# FAIO-Switch.net
KiCad netlist of a schematic drawn in EAGLE
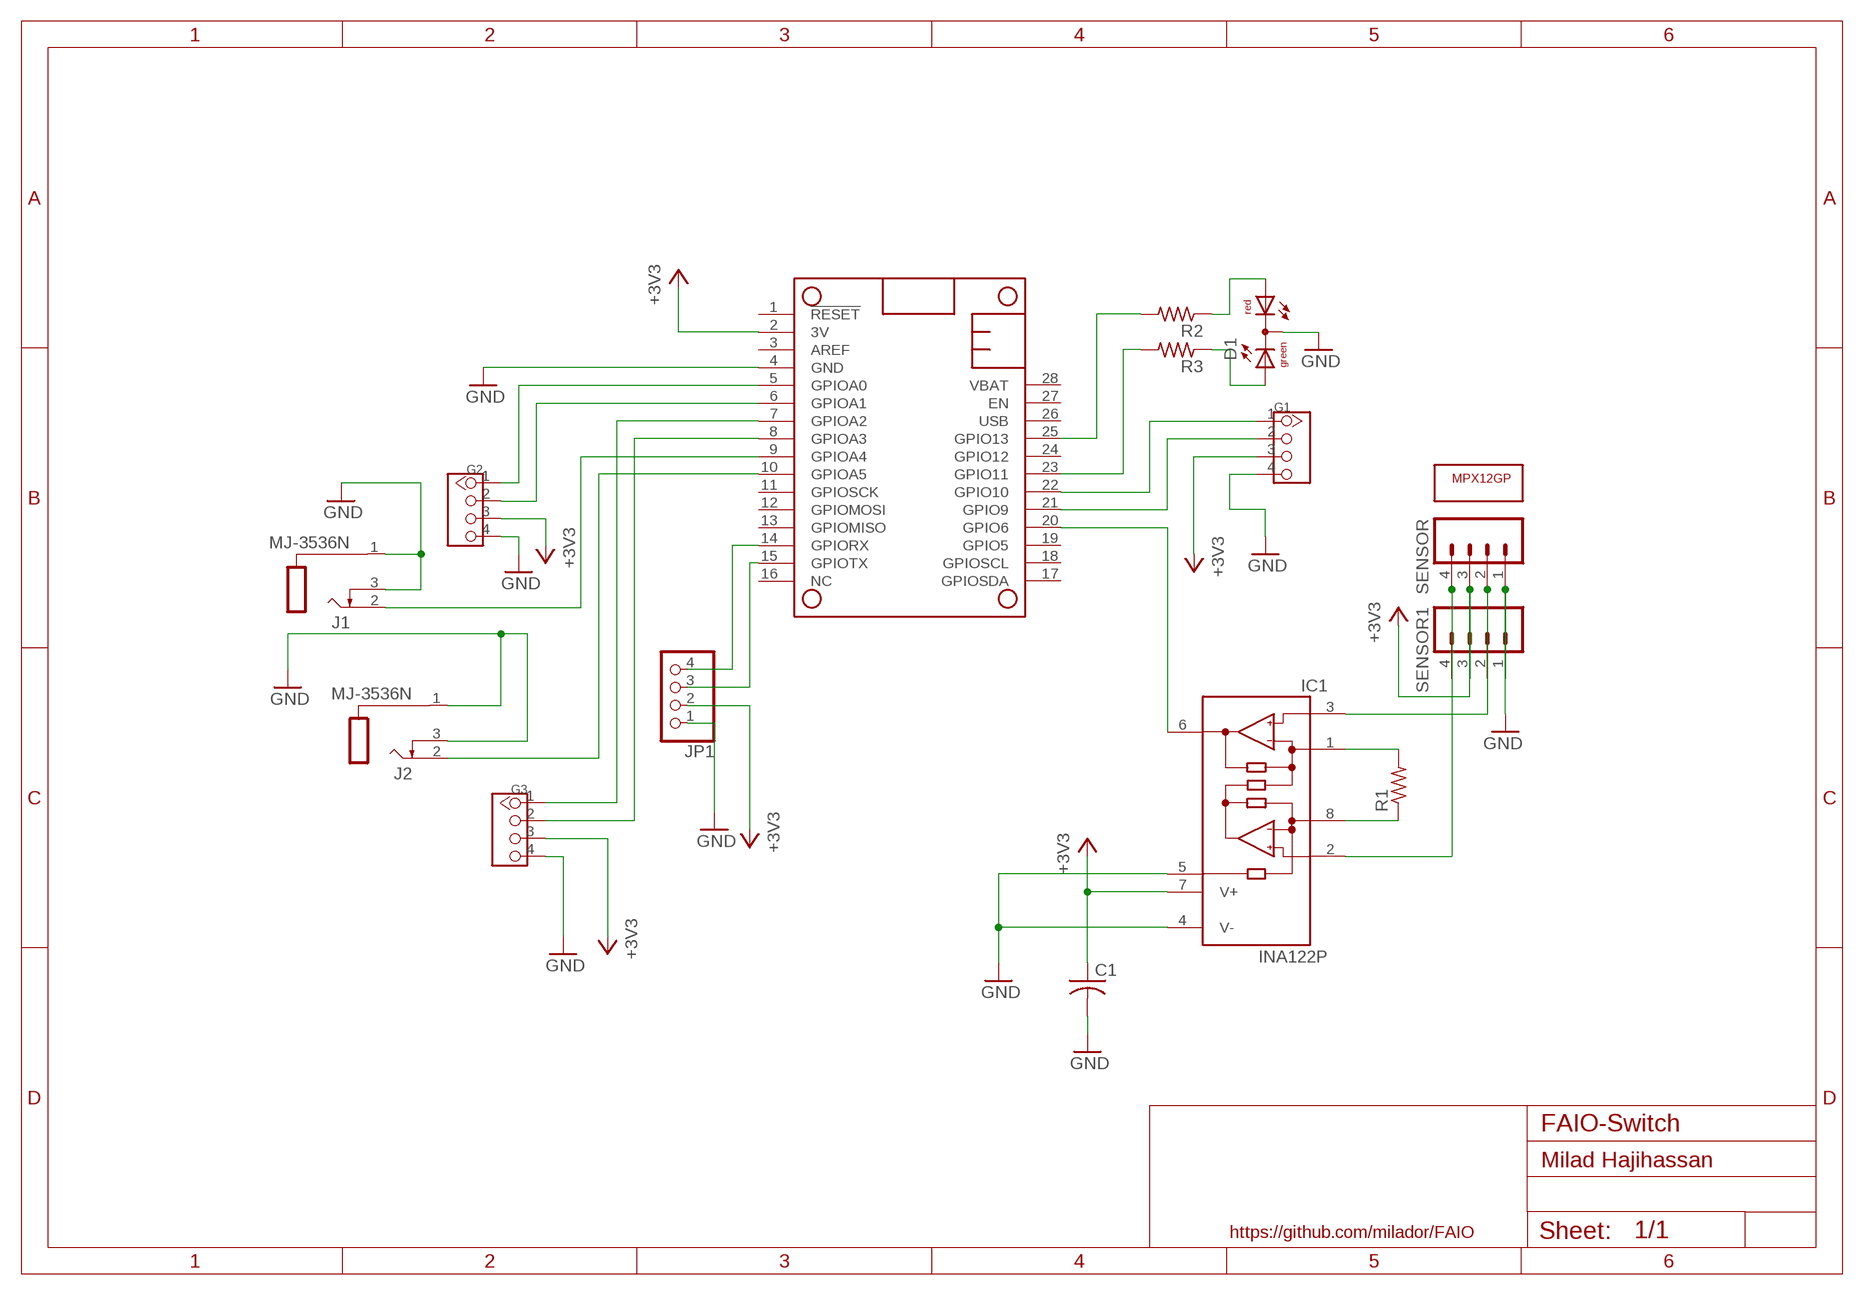
[diagram p0: schematic, sheet 1]

(export (version "E")
  (design (tool "Eeschema 10.0.6"))
  (components
    (comp (ref "C1")
      (value "C-US025-024X044")
      (footprint "eagle-import:C025-024X044")
      (libsource (lib "eagle-import") (part "C-US025-024X044"))
    )
    (comp (ref "D1")
      (value "DUOLED5MM")
      (footprint "eagle-import:DUOLED5MM")
      (libsource (lib "eagle-import") (part "DUOLED5MM"))
    )
    (comp (ref "G1")
      (value "TWIG-4P-2.0'90D'")
      (footprint "eagle-import:4P-2.0-90D")
      (libsource (lib "eagle-import") (part "TWIG-4P-2.0'90D'"))
    )
    (comp (ref "G2")
      (value "TWIG-4P-2.0'90D'")
      (footprint "eagle-import:4P-2.0-90D")
      (libsource (lib "eagle-import") (part "TWIG-4P-2.0'90D'"))
    )
    (comp (ref "G3")
      (value "TWIG-4P-2.0'90D'")
      (footprint "eagle-import:4P-2.0-90D")
      (libsource (lib "eagle-import") (part "TWIG-4P-2.0'90D'"))
    )
    (comp (ref "IC1")
      (value "INA122P")
      (footprint "eagle-import:DIL08")
      (fields (field (name "MF") "TEXAS INSTRUMENTS"))
      (libsource (lib "eagle-import") (part "INA122P"))
    )
    (comp (ref "J1")
      (value "MJ-3536N")
      (footprint "eagle-import:MJ-3536N")
      (libsource (lib "eagle-import") (part "MJ-3536N"))
    )
    (comp (ref "J2")
      (value "MJ-3536N")
      (footprint "eagle-import:MJ-3536N")
      (libsource (lib "eagle-import") (part "MJ-3536N"))
    )
    (comp (ref "JP1")
      (value "PINHD-1X4")
      (footprint "eagle-import:1X04")
      (libsource (lib "eagle-import") (part "PINHD-1X4"))
    )
    (comp (ref "MS1")
      (value "FEATHERWING_NODIM")
      (footprint "eagle-import:FEATHERWING_DIM")
      (libsource (lib "eagle-import") (part "FEATHERWING_NODIM"))
    )
    (comp (ref "R1")
      (value "R-US_0204/7")
      (footprint "eagle-import:0204_7")
      (libsource (lib "eagle-import") (part "R-US_0204/7"))
    )
    (comp (ref "R2")
      (value "R-US_0204/7")
      (footprint "eagle-import:0204_7")
      (libsource (lib "eagle-import") (part "R-US_0204/7"))
    )
    (comp (ref "R3")
      (value "R-US_0204/7")
      (footprint "eagle-import:0204_7")
      (libsource (lib "eagle-import") (part "R-US_0204/7"))
    )
    (comp (ref "SENSOR")
      (value "M04PTH")
      (footprint "eagle-import:1X04")
      (libsource (lib "eagle-import") (part "M04PTH"))
    )
    (comp (ref "SENSOR1")
      (value "M04PTH")
      (footprint "eagle-import:1X04")
      (libsource (lib "eagle-import") (part "M04PTH"))
    )
    (comp (ref "U1")
      (value "MPX12GP")
      (footprint "eagle-import:MPX12GP")
      (libsource (lib "eagle-import") (part "MPX12GP"))
    )
  )
  (nets
    (net (code "1") (name "+3V3") (class "Default")
      (node (ref "C1") (pin "1") (pinfunction "1_1") (pintype "passive"))
      (node (ref "G1") (pin "3") (pinfunction "3_3") (pintype "bidirectional"))
      (node (ref "G2") (pin "3") (pinfunction "3_3") (pintype "bidirectional"))
      (node (ref "G3") (pin "3") (pinfunction "3_3") (pintype "bidirectional"))
      (node (ref "IC1") (pin "7") (pinfunction "V+_7") (pintype "power_in"))
      (node (ref "JP1") (pin "2") (pinfunction "2_2") (pintype "passive"))
      (node (ref "MS1") (pin "2") (pinfunction "3V_2") (pintype "power_in"))
      (node (ref "SENSOR") (pin "3") (pinfunction "3_3") (pintype "passive"))
      (node (ref "SENSOR1") (pin "3") (pinfunction "3_3") (pintype "passive"))
    )
    (net (code "2") (name "/USB") (class "Default")
      (node (ref "MS1") (pin "26") (pinfunction "USB_26") (pintype "power_in"))
    )
    (net (code "3") (name "/VBAT") (class "Default")
      (node (ref "MS1") (pin "28") (pinfunction "VBAT_28") (pintype "power_in"))
    )
    (net (code "4") (name "GND") (class "Default")
      (node (ref "C1") (pin "2") (pinfunction "2_2") (pintype "passive"))
      (node (ref "D1") (pin "K") (pinfunction "C_K") (pintype "passive"))
      (node (ref "G1") (pin "4") (pinfunction "4_4") (pintype "bidirectional"))
      (node (ref "G2") (pin "4") (pinfunction "4_4") (pintype "bidirectional"))
      (node (ref "G3") (pin "4") (pinfunction "4_4") (pintype "bidirectional"))
      (node (ref "IC1") (pin "4") (pinfunction "V-_4") (pintype "power_in"))
      (node (ref "IC1") (pin "5") (pinfunction "REF_5") (pintype "passive"))
      (node (ref "J1") (pin "1") (pinfunction "S_1") (pintype "passive"))
      (node (ref "J1") (pin "3") (pinfunction "TS_3") (pintype "passive"))
      (node (ref "J2") (pin "1") (pinfunction "S_1") (pintype "passive"))
      (node (ref "J2") (pin "3") (pinfunction "TS_3") (pintype "passive"))
      (node (ref "JP1") (pin "1") (pinfunction "1_1") (pintype "passive"))
      (node (ref "MS1") (pin "4") (pinfunction "GND_4") (pintype "power_in"))
      (node (ref "SENSOR") (pin "1") (pinfunction "1_1") (pintype "passive"))
      (node (ref "SENSOR1") (pin "1") (pinfunction "1_1") (pintype "passive"))
    )
    (net (code "5") (name "Net-(D1-PadAG)") (class "Default")
      (node (ref "D1") (pin "AG") (pinfunction "AG_AG") (pintype "passive"))
      (node (ref "R3") (pin "1") (pinfunction "1_1") (pintype "passive"))
    )
    (net (code "6") (name "Net-(D1-PadAR)") (class "Default")
      (node (ref "D1") (pin "AR") (pinfunction "AR_AR") (pintype "passive"))
      (node (ref "R2") (pin "1") (pinfunction "1_1") (pintype "passive"))
    )
    (net (code "7") (name "Net-(IC1-+IN)") (class "Default")
      (node (ref "IC1") (pin "3") (pinfunction "+IN_3") (pintype "input"))
      (node (ref "SENSOR") (pin "2") (pinfunction "2_2") (pintype "passive"))
      (node (ref "SENSOR1") (pin "2") (pinfunction "2_2") (pintype "passive"))
    )
    (net (code "8") (name "Net-(IC1--IN)") (class "Default")
      (node (ref "IC1") (pin "2") (pinfunction "-IN_2") (pintype "input"))
      (node (ref "SENSOR") (pin "4") (pinfunction "4_4") (pintype "passive"))
      (node (ref "SENSOR1") (pin "4") (pinfunction "4_4") (pintype "passive"))
    )
    (net (code "9") (name "Net-(IC1-OUT)") (class "Default")
      (node (ref "IC1") (pin "6") (pinfunction "OUT_6") (pintype "output"))
      (node (ref "MS1") (pin "20") (pinfunction "GPIO6_20") (pintype "bidirectional"))
    )
    (net (code "10") (name "Net-(IC1-RG-Pad1)") (class "Default")
      (node (ref "IC1") (pin "1") (pinfunction "RG_1") (pintype "passive"))
      (node (ref "R1") (pin "2") (pinfunction "2_2") (pintype "passive"))
    )
    (net (code "11") (name "Net-(IC1-RG-Pad8)") (class "Default")
      (node (ref "IC1") (pin "8") (pinfunction "RG_8") (pintype "passive"))
      (node (ref "R1") (pin "1") (pinfunction "1_1") (pintype "passive"))
    )
    (net (code "12") (name "Net-(J1-T)") (class "Default")
      (node (ref "J1") (pin "2") (pinfunction "T_2") (pintype "passive"))
      (node (ref "MS1") (pin "9") (pinfunction "GPIOA4_9") (pintype "bidirectional"))
    )
    (net (code "13") (name "Net-(J2-T)") (class "Default")
      (node (ref "J2") (pin "2") (pinfunction "T_2") (pintype "passive"))
      (node (ref "MS1") (pin "10") (pinfunction "GPIOA5_10") (pintype "bidirectional"))
    )
    (net (code "14") (name "Net-(MS1-GPIO9)") (class "Default")
      (node (ref "G1") (pin "2") (pinfunction "2_2") (pintype "bidirectional"))
      (node (ref "MS1") (pin "21") (pinfunction "GPIO9_21") (pintype "bidirectional"))
    )
    (net (code "15") (name "Net-(MS1-GPIO10)") (class "Default")
      (node (ref "G1") (pin "1") (pinfunction "1_1") (pintype "bidirectional"))
      (node (ref "MS1") (pin "22") (pinfunction "GPIO10_22") (pintype "bidirectional"))
    )
    (net (code "16") (name "Net-(MS1-GPIO11)") (class "Default")
      (node (ref "MS1") (pin "23") (pinfunction "GPIO11_23") (pintype "bidirectional"))
      (node (ref "R3") (pin "2") (pinfunction "2_2") (pintype "passive"))
    )
    (net (code "17") (name "Net-(MS1-GPIO13)") (class "Default")
      (node (ref "MS1") (pin "25") (pinfunction "GPIO13_25") (pintype "bidirectional"))
      (node (ref "R2") (pin "2") (pinfunction "2_2") (pintype "passive"))
    )
    (net (code "18") (name "Net-(MS1-GPIOA0)") (class "Default")
      (node (ref "G2") (pin "1") (pinfunction "1_1") (pintype "bidirectional"))
      (node (ref "MS1") (pin "5") (pinfunction "GPIOA0_5") (pintype "bidirectional"))
    )
    (net (code "19") (name "Net-(MS1-GPIOA1)") (class "Default")
      (node (ref "G2") (pin "2") (pinfunction "2_2") (pintype "bidirectional"))
      (node (ref "MS1") (pin "6") (pinfunction "GPIOA1_6") (pintype "bidirectional"))
    )
    (net (code "20") (name "Net-(MS1-GPIOA2)") (class "Default")
      (node (ref "G3") (pin "1") (pinfunction "1_1") (pintype "bidirectional"))
      (node (ref "MS1") (pin "7") (pinfunction "GPIOA2_7") (pintype "bidirectional"))
    )
    (net (code "21") (name "Net-(MS1-GPIOA3)") (class "Default")
      (node (ref "G3") (pin "2") (pinfunction "2_2") (pintype "bidirectional"))
      (node (ref "MS1") (pin "8") (pinfunction "GPIOA3_8") (pintype "bidirectional"))
    )
    (net (code "22") (name "Net-(MS1-GPIORX)") (class "Default")
      (node (ref "JP1") (pin "4") (pinfunction "4_4") (pintype "passive"))
      (node (ref "MS1") (pin "14") (pinfunction "GPIORX_14") (pintype "bidirectional"))
    )
    (net (code "23") (name "Net-(MS1-GPIOTX)") (class "Default")
      (node (ref "JP1") (pin "3") (pinfunction "3_3") (pintype "passive"))
      (node (ref "MS1") (pin "15") (pinfunction "GPIOTX_15") (pintype "bidirectional"))
    )
    (net (code "24") (name "unconnected-(MS1-AREF-Pad3)") (class "Default")
      (node (ref "MS1") (pin "3") (pinfunction "AREF_3") (pintype "passive"))
    )
    (net (code "25") (name "unconnected-(MS1-EN-Pad27)") (class "Default")
      (node (ref "MS1") (pin "27") (pinfunction "EN_27") (pintype "passive"))
    )
    (net (code "26") (name "unconnected-(MS1-GPIO5-Pad19)") (class "Default")
      (node (ref "MS1") (pin "19") (pinfunction "GPIO5_19") (pintype "bidirectional"))
    )
    (net (code "27") (name "unconnected-(MS1-GPIO12-Pad24)") (class "Default")
      (node (ref "MS1") (pin "24") (pinfunction "GPIO12_24") (pintype "bidirectional"))
    )
    (net (code "28") (name "unconnected-(MS1-GPIOMISO-Pad13)") (class "Default")
      (node (ref "MS1") (pin "13") (pinfunction "GPIOMISO_13") (pintype "bidirectional"))
    )
    (net (code "29") (name "unconnected-(MS1-GPIOMOSI-Pad12)") (class "Default")
      (node (ref "MS1") (pin "12") (pinfunction "GPIOMOSI_12") (pintype "bidirectional"))
    )
    (net (code "30") (name "unconnected-(MS1-GPIOSCK-Pad11)") (class "Default")
      (node (ref "MS1") (pin "11") (pinfunction "GPIOSCK_11") (pintype "bidirectional"))
    )
    (net (code "31") (name "unconnected-(MS1-GPIOSCL-Pad18)") (class "Default")
      (node (ref "MS1") (pin "18") (pinfunction "GPIOSCL_18") (pintype "bidirectional"))
    )
    (net (code "32") (name "unconnected-(MS1-GPIOSDA-Pad17)") (class "Default")
      (node (ref "MS1") (pin "17") (pinfunction "GPIOSDA_17") (pintype "bidirectional"))
    )
    (net (code "33") (name "unconnected-(MS1-NC-Pad16)") (class "Default")
      (node (ref "MS1") (pin "16") (pinfunction "NC_16") (pintype "passive"))
    )
    (net (code "34") (name "unconnected-(MS1-~{RESET}-Pad1)") (class "Default")
      (node (ref "MS1") (pin "1") (pinfunction "~{RESET}_1") (pintype "input"))
    )
  )
)
